# Schematic.net
KiCad netlist of a schematic drawn in EAGLE
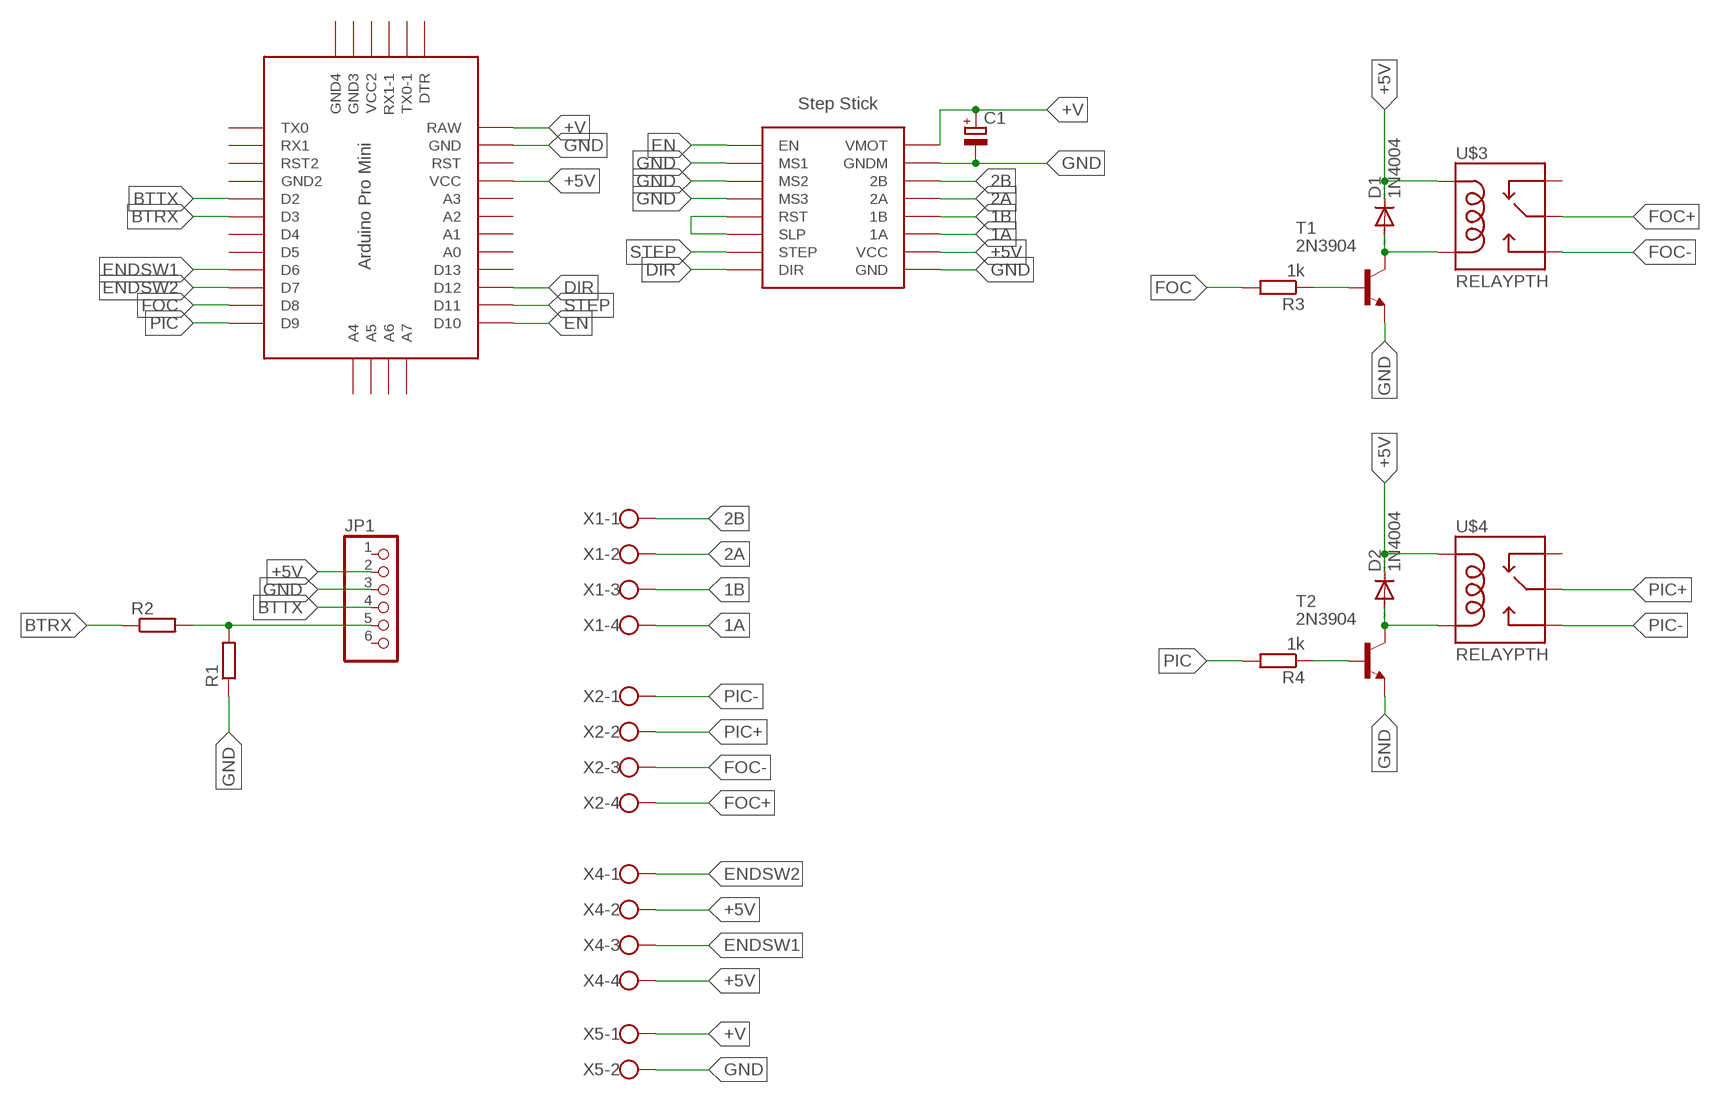
[diagram p0: schematic, sheet 1]

(export (version "E")
  (design (tool "Eeschema 10.0.6"))
  (components
    (comp (ref "C1")
      (value "CPOL-EUE2,5-6E")
      (footprint "eagle-import:E2,5-6E")
      (libsource (lib "eagle-import") (part "CPOL-EUE2,5-6E"))
    )
    (comp (ref "D1")
      (value "1N4004")
      (footprint "eagle-import:DO41-10")
      (libsource (lib "eagle-import") (part "1N4004"))
    )
    (comp (ref "D2")
      (value "1N4004")
      (footprint "eagle-import:DO41-10")
      (libsource (lib "eagle-import") (part "1N4004"))
    )
    (comp (ref "JP1")
      (value "PINHD-1X6")
      (footprint "eagle-import:1X06")
      (libsource (lib "eagle-import") (part "PINHD-1X6"))
    )
    (comp (ref "R1")
      (value "R-EU_0207/7")
      (footprint "eagle-import:0207_7")
      (libsource (lib "eagle-import") (part "R-EU_0207/7"))
    )
    (comp (ref "R2")
      (value "R-EU_0207/7")
      (footprint "eagle-import:0207_7")
      (libsource (lib "eagle-import") (part "R-EU_0207/7"))
    )
    (comp (ref "R3")
      (value "1k")
      (footprint "eagle-import:0207_7")
      (libsource (lib "eagle-import") (part "R-EU_0207/7"))
    )
    (comp (ref "R4")
      (value "1k")
      (footprint "eagle-import:0207_7")
      (libsource (lib "eagle-import") (part "R-EU_0207/7"))
    )
    (comp (ref "T1")
      (value "2N3904")
      (footprint "eagle-import:TO92")
      (libsource (lib "eagle-import") (part "2N3904"))
    )
    (comp (ref "T2")
      (value "2N3904")
      (footprint "eagle-import:TO92")
      (libsource (lib "eagle-import") (part "2N3904"))
    )
    (comp (ref "U$1")
      (value "PRO-MINI")
      (footprint "eagle-import:PRO-MINI")
      (libsource (lib "eagle-import") (part "PRO-MINI"))
    )
    (comp (ref "U$2")
      (value "STEP-STICK")
      (footprint "eagle-import:STEP-STICK")
      (libsource (lib "eagle-import") (part "STEP-STICK"))
    )
    (comp (ref "U$3")
      (value "RELAYPTH")
      (footprint "eagle-import:SRD-05VDC-SL-C")
      (libsource (lib "eagle-import") (part "RELAYPTH"))
    )
    (comp (ref "U$4")
      (value "RELAYPTH")
      (footprint "eagle-import:SRD-05VDC-SL-C")
      (libsource (lib "eagle-import") (part "RELAYPTH"))
    )
    (comp (ref "X1")
      (value "W237-4")
      (footprint "eagle-import:W237-4")
      (libsource (lib "eagle-import") (part "W237-4"))
    )
    (comp (ref "X2")
      (value "W237-4")
      (footprint "eagle-import:W237-4")
      (libsource (lib "eagle-import") (part "W237-4"))
    )
    (comp (ref "X4")
      (value "W237-4")
      (footprint "eagle-import:W237-4")
      (libsource (lib "eagle-import") (part "W237-4"))
    )
    (comp (ref "X5")
      (value "W237-102")
      (footprint "eagle-import:W237-102")
      (fields (field (name "MPN") "237-102"))
      (libsource (lib "eagle-import") (part "W237-102"))
    )
  )
  (nets
    (net (code "1") (name "+5V") (class "Default")
      (node (ref "D1") (pin "C") (pinfunction "C_C") (pintype "passive"))
      (node (ref "D2") (pin "C") (pinfunction "C_C") (pintype "passive"))
      (node (ref "JP1") (pin "2") (pinfunction "2_2") (pintype "passive"))
      (node (ref "U$1") (pin "VCC") (pinfunction "VCC_VCC") (pintype "bidirectional"))
      (node (ref "U$2") (pin "VCC") (pinfunction "VCC_VCC") (pintype "bidirectional"))
      (node (ref "U$3") (pin "COIL1") (pinfunction "COIL1_COIL1") (pintype "bidirectional"))
      (node (ref "U$4") (pin "COIL1") (pinfunction "COIL1_COIL1") (pintype "bidirectional"))
      (node (ref "X4") (pin "2") (pinfunction "KL_2") (pintype "passive"))
      (node (ref "X4") (pin "4") (pinfunction "KL_4") (pintype "passive"))
    )
    (net (code "2") (name "+V") (class "Default")
      (node (ref "C1") (pin "+") (pinfunction "+_+") (pintype "passive"))
      (node (ref "U$1") (pin "RAW") (pinfunction "RAW_RAW") (pintype "power_in"))
      (node (ref "U$2") (pin "VMOT") (pinfunction "VMOT_VMOT") (pintype "bidirectional"))
      (node (ref "X5") (pin "1") (pinfunction "KL_1") (pintype "passive"))
    )
    (net (code "3") (name "1A") (class "Default")
      (node (ref "U$2") (pin "1A") (pinfunction "1A_1A") (pintype "bidirectional"))
      (node (ref "X1") (pin "4") (pinfunction "KL_4") (pintype "passive"))
    )
    (net (code "4") (name "1B") (class "Default")
      (node (ref "U$2") (pin "1B") (pinfunction "1B_1B") (pintype "bidirectional"))
      (node (ref "X1") (pin "3") (pinfunction "KL_3") (pintype "passive"))
    )
    (net (code "5") (name "2A") (class "Default")
      (node (ref "U$2") (pin "2A") (pinfunction "2A_2A") (pintype "bidirectional"))
      (node (ref "X1") (pin "2") (pinfunction "KL_2") (pintype "passive"))
    )
    (net (code "6") (name "2B") (class "Default")
      (node (ref "U$2") (pin "2B") (pinfunction "2B_2B") (pintype "bidirectional"))
      (node (ref "X1") (pin "1") (pinfunction "KL_1") (pintype "passive"))
    )
    (net (code "7") (name "BTRX") (class "Default")
      (node (ref "R2") (pin "1") (pinfunction "1_1") (pintype "passive"))
      (node (ref "U$1") (pin "D3") (pinfunction "D3_D3") (pintype "bidirectional"))
    )
    (net (code "8") (name "BTTX") (class "Default")
      (node (ref "JP1") (pin "4") (pinfunction "4_4") (pintype "passive"))
      (node (ref "U$1") (pin "D2") (pinfunction "D2_D2") (pintype "bidirectional"))
    )
    (net (code "9") (name "DIR") (class "Default")
      (node (ref "U$1") (pin "D12") (pinfunction "D12_D12") (pintype "bidirectional"))
      (node (ref "U$2") (pin "DIR") (pinfunction "DIR_DIR") (pintype "bidirectional"))
    )
    (net (code "10") (name "EN") (class "Default")
      (node (ref "U$1") (pin "D10") (pinfunction "D10_D10") (pintype "bidirectional"))
      (node (ref "U$2") (pin "EN") (pinfunction "EN_EN") (pintype "bidirectional"))
    )
    (net (code "11") (name "ENDSW1") (class "Default")
      (node (ref "U$1") (pin "D6") (pinfunction "D6_D6") (pintype "bidirectional"))
      (node (ref "X4") (pin "3") (pinfunction "KL_3") (pintype "passive"))
    )
    (net (code "12") (name "ENDSW2") (class "Default")
      (node (ref "U$1") (pin "D7") (pinfunction "D7_D7") (pintype "bidirectional"))
      (node (ref "X4") (pin "1") (pinfunction "KL_1") (pintype "passive"))
    )
    (net (code "13") (name "FOC") (class "Default")
      (node (ref "R3") (pin "2") (pinfunction "2_2") (pintype "passive"))
      (node (ref "U$1") (pin "D8") (pinfunction "D8_D8") (pintype "bidirectional"))
    )
    (net (code "14") (name "FOC+") (class "Default")
      (node (ref "U$3") (pin "SWCOMMON") (pinfunction "SWCOMMON_SWCOMMON") (pintype "bidirectional"))
      (node (ref "X2") (pin "4") (pinfunction "KL_4") (pintype "passive"))
    )
    (net (code "15") (name "FOC-") (class "Default")
      (node (ref "U$3") (pin "SWOPEN") (pinfunction "SWOPEN_SWOPEN") (pintype "bidirectional"))
      (node (ref "X2") (pin "3") (pinfunction "KL_3") (pintype "passive"))
    )
    (net (code "16") (name "GND") (class "Default")
      (node (ref "C1") (pin "-") (pinfunction "-_-") (pintype "passive"))
      (node (ref "JP1") (pin "3") (pinfunction "3_3") (pintype "passive"))
      (node (ref "R1") (pin "1") (pinfunction "1_1") (pintype "passive"))
      (node (ref "T1") (pin "3") (pinfunction "E_3") (pintype "passive"))
      (node (ref "T2") (pin "3") (pinfunction "E_3") (pintype "passive"))
      (node (ref "U$1") (pin "GND") (pinfunction "GND_GND") (pintype "input"))
      (node (ref "U$2") (pin "GND") (pinfunction "GND_GND") (pintype "bidirectional"))
      (node (ref "U$2") (pin "GNDM") (pinfunction "GNDM_GNDM") (pintype "bidirectional"))
      (node (ref "U$2") (pin "MS1") (pinfunction "MS1_MS1") (pintype "bidirectional"))
      (node (ref "U$2") (pin "MS2") (pinfunction "MS2_MS2") (pintype "bidirectional"))
      (node (ref "U$2") (pin "MS3") (pinfunction "MS3_MS3") (pintype "bidirectional"))
      (node (ref "X5") (pin "2") (pinfunction "KL_2") (pintype "passive"))
    )
    (net (code "17") (name "Net-(JP1-Pad5)") (class "Default")
      (node (ref "JP1") (pin "5") (pinfunction "5_5") (pintype "passive"))
      (node (ref "R1") (pin "2") (pinfunction "2_2") (pintype "passive"))
      (node (ref "R2") (pin "2") (pinfunction "2_2") (pintype "passive"))
    )
    (net (code "18") (name "Net-(T1-B)") (class "Default")
      (node (ref "R3") (pin "1") (pinfunction "1_1") (pintype "passive"))
      (node (ref "T1") (pin "2") (pinfunction "B_2") (pintype "passive"))
    )
    (net (code "19") (name "Net-(T1-C)") (class "Default")
      (node (ref "D1") (pin "A") (pinfunction "A_A") (pintype "passive"))
      (node (ref "T1") (pin "1") (pinfunction "C_1") (pintype "passive"))
      (node (ref "U$3") (pin "COIL0") (pinfunction "COIL0_COIL0") (pintype "bidirectional"))
    )
    (net (code "20") (name "Net-(T2-B)") (class "Default")
      (node (ref "R4") (pin "1") (pinfunction "1_1") (pintype "passive"))
      (node (ref "T2") (pin "2") (pinfunction "B_2") (pintype "passive"))
    )
    (net (code "21") (name "Net-(T2-C)") (class "Default")
      (node (ref "D2") (pin "A") (pinfunction "A_A") (pintype "passive"))
      (node (ref "T2") (pin "1") (pinfunction "C_1") (pintype "passive"))
      (node (ref "U$4") (pin "COIL0") (pinfunction "COIL0_COIL0") (pintype "bidirectional"))
    )
    (net (code "22") (name "Net-(U$2-PadRST)") (class "Default")
      (node (ref "U$2") (pin "RST") (pinfunction "RST_RST") (pintype "bidirectional"))
      (node (ref "U$2") (pin "SLP") (pinfunction "SLP_SLP") (pintype "bidirectional"))
    )
    (net (code "23") (name "PIC") (class "Default")
      (node (ref "R4") (pin "2") (pinfunction "2_2") (pintype "passive"))
      (node (ref "U$1") (pin "D9") (pinfunction "D9_D9") (pintype "bidirectional"))
    )
    (net (code "24") (name "PIC+") (class "Default")
      (node (ref "U$4") (pin "SWCOMMON") (pinfunction "SWCOMMON_SWCOMMON") (pintype "bidirectional"))
      (node (ref "X2") (pin "2") (pinfunction "KL_2") (pintype "passive"))
    )
    (net (code "25") (name "PIC-") (class "Default")
      (node (ref "U$4") (pin "SWOPEN") (pinfunction "SWOPEN_SWOPEN") (pintype "bidirectional"))
      (node (ref "X2") (pin "1") (pinfunction "KL_1") (pintype "passive"))
    )
    (net (code "26") (name "STEP") (class "Default")
      (node (ref "U$1") (pin "D11") (pinfunction "D11_D11") (pintype "bidirectional"))
      (node (ref "U$2") (pin "SPT") (pinfunction "STEP_SPT") (pintype "bidirectional"))
    )
    (net (code "27") (name "unconnected-(JP1-Pad1)") (class "Default")
      (node (ref "JP1") (pin "1") (pinfunction "1_1") (pintype "passive"))
    )
    (net (code "28") (name "unconnected-(JP1-Pad6)") (class "Default")
      (node (ref "JP1") (pin "6") (pinfunction "6_6") (pintype "passive"))
    )
    (net (code "29") (name "unconnected-(U$1-GND2-PadGND1)") (class "Default")
      (node (ref "U$1") (pin "GND1") (pinfunction "GND2_GND1") (pintype "bidirectional"))
    )
    (net (code "30") (name "unconnected-(U$1-GND4-PadGND2)") (class "Default")
      (node (ref "U$1") (pin "GND2") (pinfunction "GND4_GND2") (pintype "bidirectional"))
    )
    (net (code "31") (name "unconnected-(U$1-PadA0)") (class "Default")
      (node (ref "U$1") (pin "A0") (pinfunction "A0_A0") (pintype "bidirectional"))
    )
    (net (code "32") (name "unconnected-(U$1-PadA1)") (class "Default")
      (node (ref "U$1") (pin "A1") (pinfunction "A1_A1") (pintype "bidirectional"))
    )
    (net (code "33") (name "unconnected-(U$1-PadA2)") (class "Default")
      (node (ref "U$1") (pin "A2") (pinfunction "A2_A2") (pintype "bidirectional"))
    )
    (net (code "34") (name "unconnected-(U$1-PadA3)") (class "Default")
      (node (ref "U$1") (pin "A3") (pinfunction "A3_A3") (pintype "bidirectional"))
    )
    (net (code "35") (name "unconnected-(U$1-PadA4)") (class "Default")
      (node (ref "U$1") (pin "A4") (pinfunction "A4_A4") (pintype "bidirectional"))
    )
    (net (code "36") (name "unconnected-(U$1-PadA5)") (class "Default")
      (node (ref "U$1") (pin "A5") (pinfunction "A5_A5") (pintype "bidirectional"))
    )
    (net (code "37") (name "unconnected-(U$1-PadA6)") (class "Default")
      (node (ref "U$1") (pin "A6") (pinfunction "A6_A6") (pintype "bidirectional"))
    )
    (net (code "38") (name "unconnected-(U$1-PadA7)") (class "Default")
      (node (ref "U$1") (pin "A7") (pinfunction "A7_A7") (pintype "bidirectional"))
    )
    (net (code "39") (name "unconnected-(U$1-PadD4)") (class "Default")
      (node (ref "U$1") (pin "D4") (pinfunction "D4_D4") (pintype "bidirectional"))
    )
    (net (code "40") (name "unconnected-(U$1-PadD5)") (class "Default")
      (node (ref "U$1") (pin "D5") (pinfunction "D5_D5") (pintype "bidirectional"))
    )
    (net (code "41") (name "unconnected-(U$1-PadD13)") (class "Default")
      (node (ref "U$1") (pin "D13") (pinfunction "D13_D13") (pintype "bidirectional"))
    )
    (net (code "42") (name "unconnected-(U$1-PadDTR)") (class "Default")
      (node (ref "U$1") (pin "DTR") (pinfunction "DTR_DTR") (pintype "bidirectional"))
    )
    (net (code "43") (name "unconnected-(U$1-PadGND3)") (class "Default")
      (node (ref "U$1") (pin "GND3") (pinfunction "GND3_GND3") (pintype "bidirectional"))
    )
    (net (code "44") (name "unconnected-(U$1-PadRST)") (class "Default")
      (node (ref "U$1") (pin "RST") (pinfunction "RST_RST") (pintype "bidirectional"))
    )
    (net (code "45") (name "unconnected-(U$1-PadRX1)") (class "Default")
      (node (ref "U$1") (pin "RX1") (pinfunction "RX1_RX1") (pintype "bidirectional"))
    )
    (net (code "46") (name "unconnected-(U$1-PadRX1-1)") (class "Default")
      (node (ref "U$1") (pin "RX1-1") (pinfunction "RX1-1_RX1-1") (pintype "bidirectional"))
    )
    (net (code "47") (name "unconnected-(U$1-PadTX0)") (class "Default")
      (node (ref "U$1") (pin "TX0") (pinfunction "TX0_TX0") (pintype "bidirectional"))
    )
    (net (code "48") (name "unconnected-(U$1-PadTX0-1)") (class "Default")
      (node (ref "U$1") (pin "TX0-1") (pinfunction "TX0-1_TX0-1") (pintype "bidirectional"))
    )
    (net (code "49") (name "unconnected-(U$1-RST2-PadRST1)") (class "Default")
      (node (ref "U$1") (pin "RST1") (pinfunction "RST2_RST1") (pintype "bidirectional"))
    )
    (net (code "50") (name "unconnected-(U$1-VCC2-PadVCC1)") (class "Default")
      (node (ref "U$1") (pin "VCC1") (pinfunction "VCC2_VCC1") (pintype "bidirectional"))
    )
    (net (code "51") (name "unconnected-(U$3-SWCLOSE-PadSWCLOSED)") (class "Default")
      (node (ref "U$3") (pin "SWCLOSED") (pinfunction "SWCLOSE_SWCLOSED") (pintype "bidirectional"))
    )
    (net (code "52") (name "unconnected-(U$4-SWCLOSE-PadSWCLOSED)") (class "Default")
      (node (ref "U$4") (pin "SWCLOSED") (pinfunction "SWCLOSE_SWCLOSED") (pintype "bidirectional"))
    )
  )
)
